# EtherCAT_Sheet.net
KiCad netlist of a schematic drawn in Altium Designer
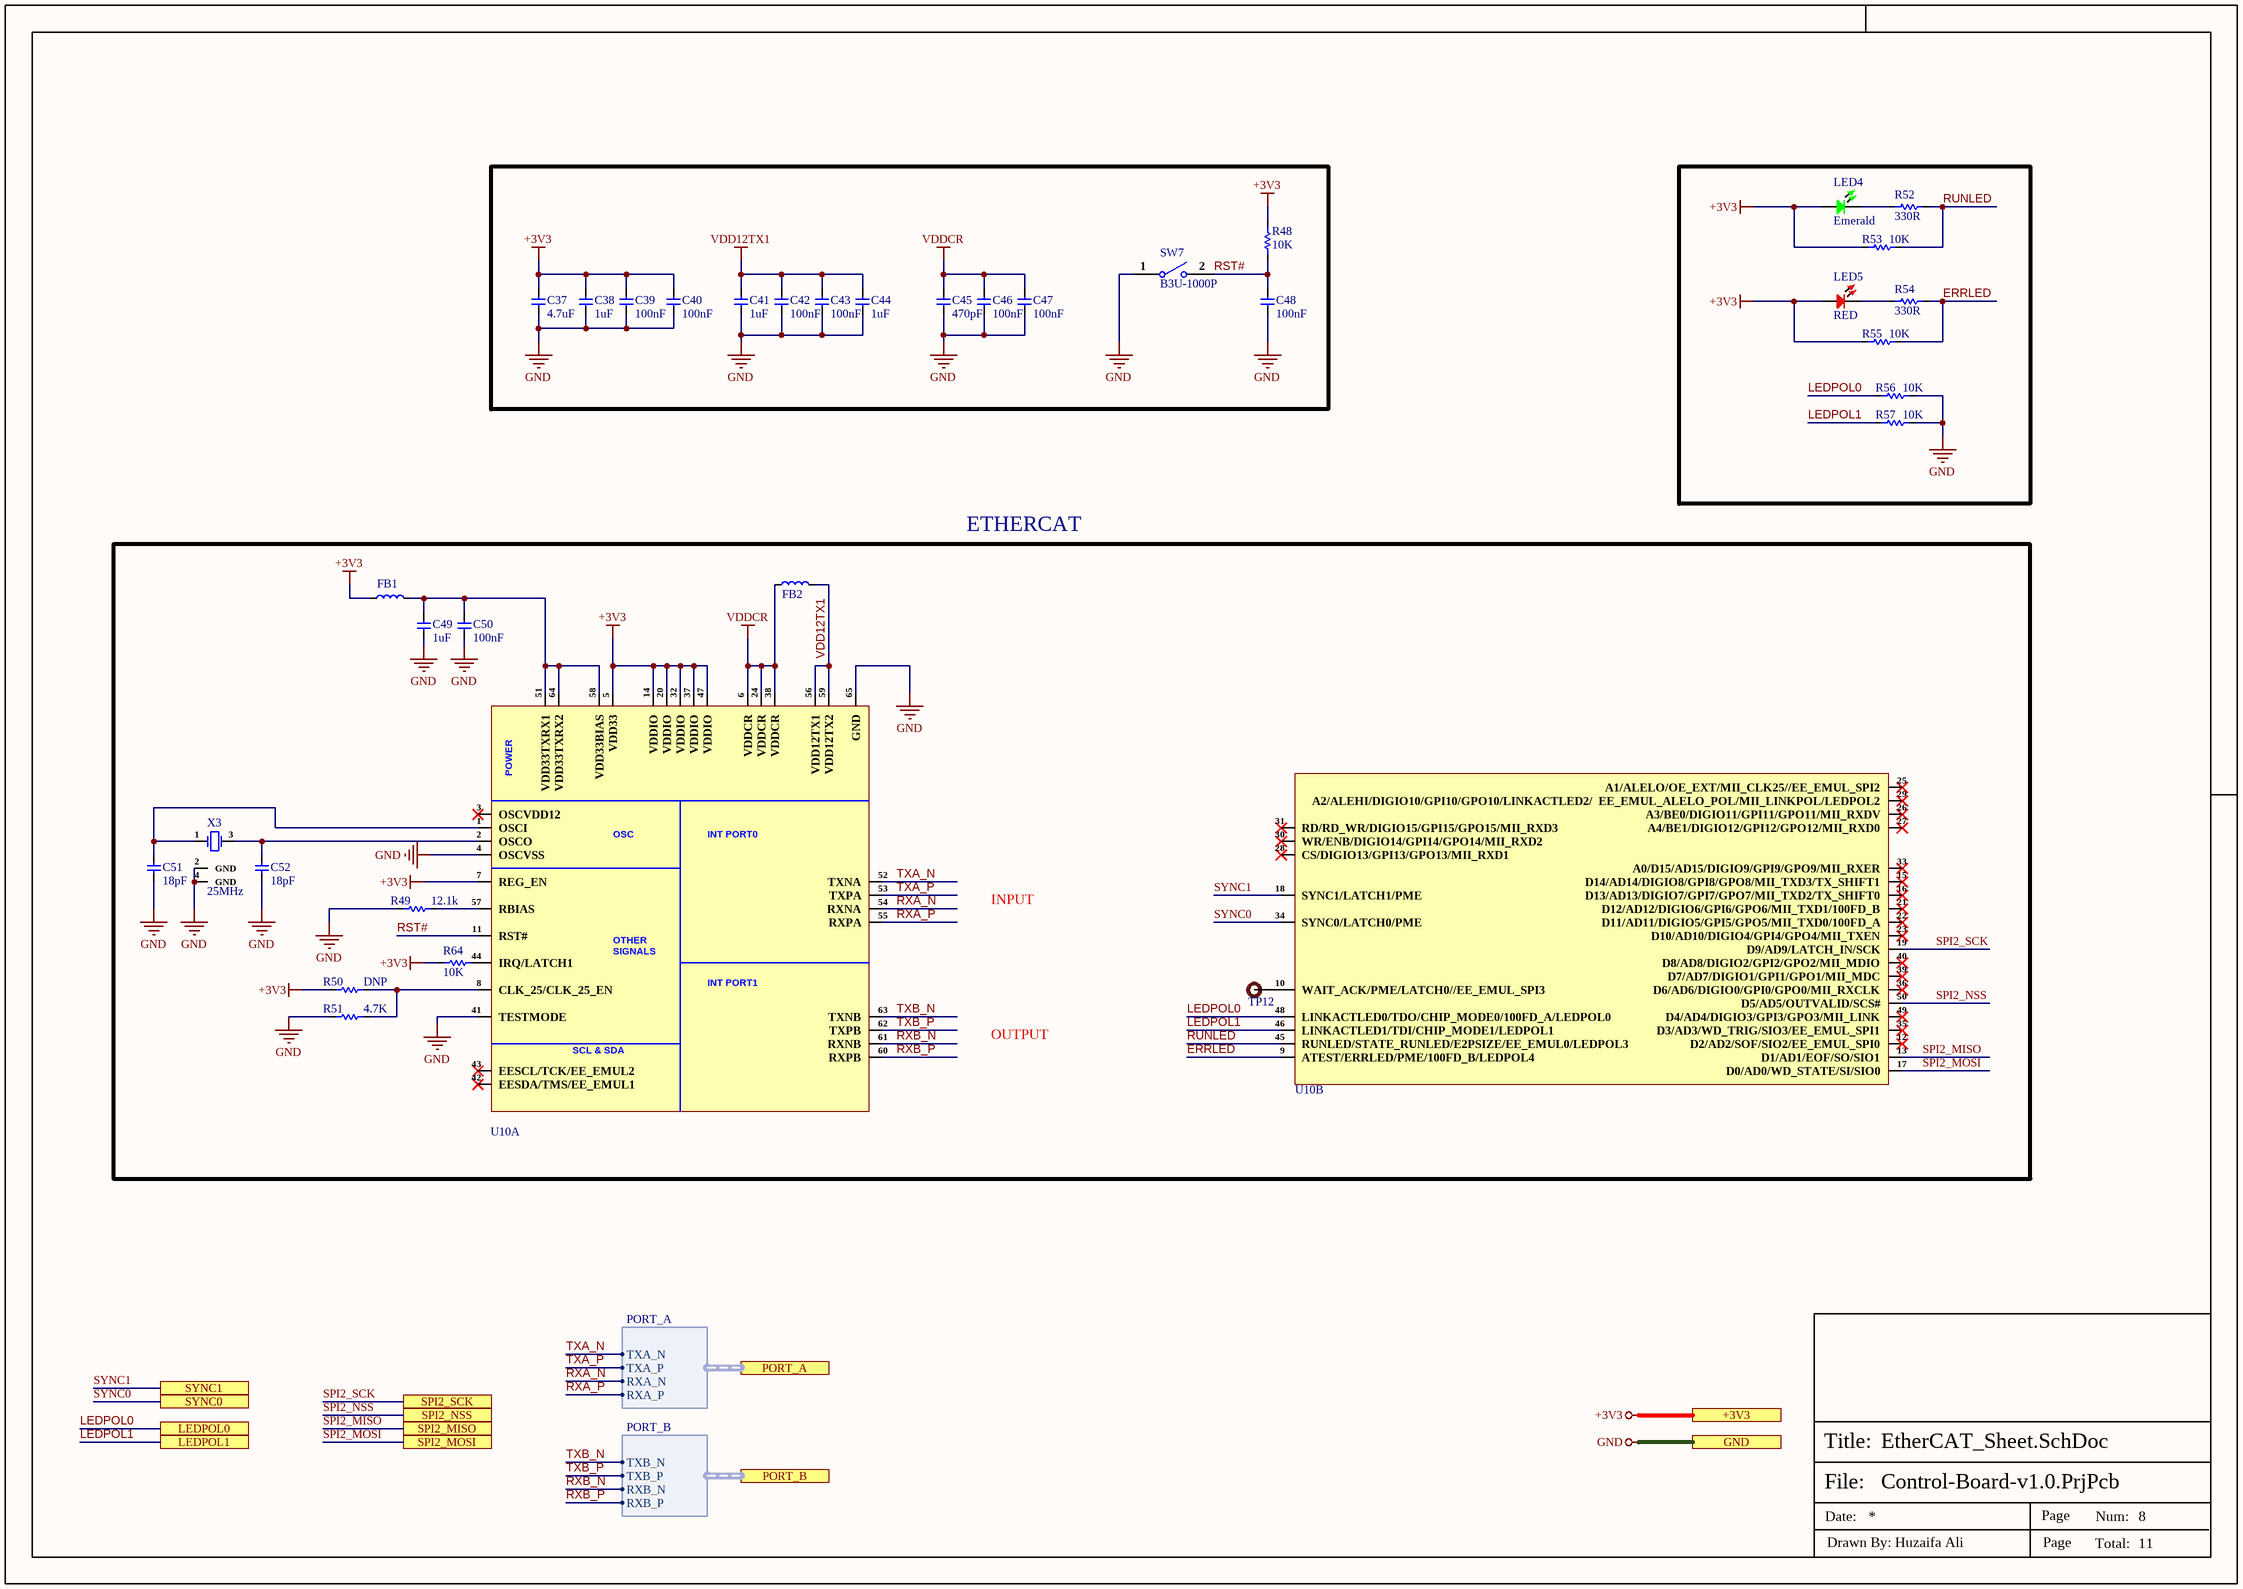
[diagram p0: EtherCAT_Sheet.SchDoc]

(export (version "E")
  (design (tool "Eeschema 10.0.6"))
  (components
    (comp (ref "C37")
      (value "4.7uF")
      (footprint "Cap-0402")
      (description "CAP CER 4.7UF 10V X5R 0402")
      (fields
        (field (name "MANUFACTURER") "Yageo")
        (field (name "MANUFACTURER PART NUMBER") "CC0402KRX5R6BB475")
      )
      (libsource (lib "eSpark Libraries") (part "CC0402KRX5R6BB475"))
    )
    (comp (ref "C38")
      (value "1uF")
      (footprint "Cap-0402")
      (description "CAP CER 1UF 10V X5R 0402")
      (fields
        (field (name "MANUFACTURER") "Yageo")
        (field (name "MANUFACTURER PART NUMBER") "CC0402KRX5R6BB105")
      )
      (libsource (lib "eSpark Libraries") (part "CC0402KRX5R6BB105"))
    )
    (comp (ref "C39")
      (value "100nF")
      (footprint "cap-0402")
      (description "CAP CER 0.1UF 50V X7R 0402")
      (fields
        (field (name "MANUFACTURER") "TDK")
        (field (name "MANUFACTURER PART NUMBER") "C1005X7R1H104KT000F")
      )
      (libsource (lib "eSpark Libraries") (part "C1005X7R1H104KT000F"))
    )
    (comp (ref "C40")
      (value "100nF")
      (footprint "cap-0402")
      (description "CAP CER 0.1UF 50V X7R 0402")
      (fields
        (field (name "MANUFACTURER") "TDK")
        (field (name "MANUFACTURER PART NUMBER") "C1005X7R1H104KT000F")
      )
      (libsource (lib "eSpark Libraries") (part "C1005X7R1H104KT000F"))
    )
    (comp (ref "C41")
      (value "1uF")
      (footprint "Cap-0402")
      (description "CAP CER 1UF 10V X5R 0402")
      (fields
        (field (name "MANUFACTURER") "Yageo")
        (field (name "MANUFACTURER PART NUMBER") "CC0402KRX5R6BB105")
      )
      (libsource (lib "eSpark Libraries") (part "CC0402KRX5R6BB105"))
    )
    (comp (ref "C42")
      (value "100nF")
      (footprint "cap-0402")
      (description "CAP CER 0.1UF 50V X7R 0402")
      (fields
        (field (name "MANUFACTURER") "TDK")
        (field (name "MANUFACTURER PART NUMBER") "C1005X7R1H104KT000F")
      )
      (libsource (lib "eSpark Libraries") (part "C1005X7R1H104KT000F"))
    )
    (comp (ref "C43")
      (value "100nF")
      (footprint "cap-0402")
      (description "CAP CER 0.1UF 50V X7R 0402")
      (fields
        (field (name "MANUFACTURER") "TDK")
        (field (name "MANUFACTURER PART NUMBER") "C1005X7R1H104KT000F")
      )
      (libsource (lib "eSpark Libraries") (part "C1005X7R1H104KT000F"))
    )
    (comp (ref "C44")
      (value "1uF")
      (footprint "Cap-0402")
      (description "CAP CER 1UF 10V X5R 0402")
      (fields
        (field (name "MANUFACTURER") "Yageo")
        (field (name "MANUFACTURER PART NUMBER") "CC0402KRX5R6BB105")
      )
      (libsource (lib "eSpark Libraries") (part "CC0402KRX5R6BB105"))
    )
    (comp (ref "C45")
      (value "470pF")
      (footprint "Cap-0603")
      (description "CAP CER 470PF 50V X7R 0603")
      (fields
        (field (name "MANUFACTURER") "Walsin Technologies")
        (field (name "MANUFACTURER PART NUMBER") "0603B471K500CT")
      )
      (libsource (lib "eSpark Libraries") (part "0603B471K500CT"))
    )
    (comp (ref "C46")
      (value "100nF")
      (footprint "cap-0402")
      (description "CAP CER 0.1UF 50V X7R 0402")
      (fields
        (field (name "MANUFACTURER") "TDK")
        (field (name "MANUFACTURER PART NUMBER") "C1005X7R1H104KT000F")
      )
      (libsource (lib "eSpark Libraries") (part "C1005X7R1H104KT000F"))
    )
    (comp (ref "C47")
      (value "100nF")
      (footprint "cap-0402")
      (description "CAP CER 0.1UF 50V X7R 0402")
      (fields
        (field (name "MANUFACTURER") "TDK")
        (field (name "MANUFACTURER PART NUMBER") "C1005X7R1H104KT000F")
      )
      (libsource (lib "eSpark Libraries") (part "C1005X7R1H104KT000F"))
    )
    (comp (ref "C48")
      (value "100nF")
      (footprint "cap-0402")
      (description "CAP CER 0.1UF 50V X7R 0402")
      (fields
        (field (name "MANUFACTURER") "TDK")
        (field (name "MANUFACTURER PART NUMBER") "C1005X7R1H104KT000F")
      )
      (libsource (lib "eSpark Libraries") (part "C1005X7R1H104KT000F"))
    )
    (comp (ref "C49")
      (value "1uF")
      (footprint "Cap-0402")
      (description "CAP CER 1UF 10V X5R 0402")
      (fields
        (field (name "MANUFACTURER") "Yageo")
        (field (name "MANUFACTURER PART NUMBER") "CC0402KRX5R6BB105")
      )
      (libsource (lib "eSpark Libraries") (part "CC0402KRX5R6BB105"))
    )
    (comp (ref "C50")
      (value "100nF")
      (footprint "cap-0402")
      (description "CAP CER 0.1UF 50V X7R 0402")
      (fields
        (field (name "MANUFACTURER") "TDK")
        (field (name "MANUFACTURER PART NUMBER") "C1005X7R1H104KT000F")
      )
      (libsource (lib "eSpark Libraries") (part "C1005X7R1H104KT000F"))
    )
    (comp (ref "C51")
      (value "18pF")
      (footprint "Cap-0402")
      (description "CAP CER 18PF 50V C0G/NP0 0402")
      (fields
        (field (name "MANUFACTURER") "Murata")
        (field (name "MANUFACTURER PART NUMBER") "GCM1555C1H180GA16D")
      )
      (libsource (lib "eSpark Libraries") (part "GCM1555C1H180GA16D"))
    )
    (comp (ref "C52")
      (value "18pF")
      (footprint "Cap-0402")
      (description "CAP CER 18PF 50V C0G/NP0 0402")
      (fields
        (field (name "MANUFACTURER") "Murata")
        (field (name "MANUFACTURER PART NUMBER") "GCM1555C1H180GA16D")
      )
      (libsource (lib "eSpark Libraries") (part "GCM1555C1H180GA16D"))
    )
    (comp (ref "FB1")
      (value "BLM15PG100SN1D")
      (footprint "IND-0402")
      (description "FERRITE BEAD 10 OHM 0402 1LN")
      (fields (field (name "MANUFACTURER") "Murata") (field (name "TOLERANCE") "25%"))
      (libsource (lib "eSpark Libraries") (part "BLM15PG100SN1D"))
    )
    (comp (ref "FB2")
      (value "BLM15PG100SN1D")
      (footprint "IND-0402")
      (description "FERRITE BEAD 10 OHM 0402 1LN")
      (fields (field (name "MANUFACTURER") "Murata") (field (name "TOLERANCE") "25%"))
      (libsource (lib "eSpark Libraries") (part "BLM15PG100SN1D"))
    )
    (comp (ref "LED4")
      (value "Emerald")
      (footprint "LED-0603")
      (description "Emerald 0603 Light Emitting Diodes (LED) ROHS")
      (fields
        (field (name "MANUFACTURER") "Foshan NationStar Optoelectronics")
        (field (name "MANUFACTURER PART NUMBER") "NCD0603G2")
      )
      (libsource (lib "eSpark Libraries") (part "NCD0603G2"))
    )
    (comp (ref "LED5")
      (value "RED")
      (footprint "LED-0603")
      (description "RED LED 0603 Light Emitting Diodes")
      (fields
        (field (name "MANUFACTURER") "Foshan NationStar Optoelectronics")
        (field (name "MANUFACTURER PART NUMBER") "NCD0603R3")
      )
      (libsource (lib "eSpark Libraries") (part "NCD0603R3"))
    )
    (comp (ref "R48")
      (value "10K")
      (footprint "Res-0402")
      (description "RES 10K OHM 1% 1/16W 0402")
      (fields
        (field (name "MANUFACTURER") "Yageo")
        (field (name "MANUFACTURER PART NUMBER") "RC0402FR-0710KL")
      )
      (libsource (lib "eSpark Libraries") (part "RC0402FR-0710KL"))
    )
    (comp (ref "R49")
      (value "12.1k")
      (footprint "Res-0402")
      (description "RES SMD 12.1KOHM 0.1% 1/16W 0402")
      (fields
        (field (name "MANUFACTURER") "Yageo")
        (field (name "MANUFACTURER PART NUMBER") "RT0402BRD0712K1L")
      )
      (libsource (lib "eSpark Libraries") (part "RT0402BRD0712K1L"))
    )
    (comp (ref "R50")
      (value "DNP")
      (footprint "Res-0402")
      (description "RES 4.7K OHM 1% 1/16W 0402")
      (fields
        (field (name "MANUFACTURER") "Yageo")
        (field (name "MANUFACTURER PART NUMBER") "RC0402FR-074K7L")
      )
      (libsource (lib "eSpark Libraries") (part "RC0402FR-074K7L"))
    )
    (comp (ref "R51")
      (value "4.7K")
      (footprint "Res-0402")
      (description "RES 4.7K OHM 1% 1/16W 0402")
      (fields
        (field (name "MANUFACTURER") "Yageo")
        (field (name "MANUFACTURER PART NUMBER") "RC0402FR-074K7L")
      )
      (libsource (lib "eSpark Libraries") (part "RC0402FR-074K7L"))
    )
    (comp (ref "R52")
      (value "330R")
      (footprint "Res-0603")
      (description "RES  SMD 330R 100 mW 0603")
      (fields
        (field (name "MANUFACTURER") "Yageo")
        (field (name "MANUFACTURER PART NUMBER") "RC0603JR-07330RL")
      )
      (libsource (lib "eSpark Libraries") (part "RC0603JR-07330RL"))
    )
    (comp (ref "R53")
      (value "10K")
      (footprint "Res-0402")
      (description "RES 10K OHM 1% 1/16W 0402")
      (fields
        (field (name "MANUFACTURER") "Yageo")
        (field (name "MANUFACTURER PART NUMBER") "RC0402FR-0710KL")
      )
      (libsource (lib "eSpark Libraries") (part "RC0402FR-0710KL"))
    )
    (comp (ref "R54")
      (value "330R")
      (footprint "Res-0603")
      (description "RES  SMD 330R 100 mW 0603")
      (fields
        (field (name "MANUFACTURER") "Yageo")
        (field (name "MANUFACTURER PART NUMBER") "RC0603JR-07330RL")
      )
      (libsource (lib "eSpark Libraries") (part "RC0603JR-07330RL"))
    )
    (comp (ref "R55")
      (value "10K")
      (footprint "Res-0402")
      (description "RES 10K OHM 1% 1/16W 0402")
      (fields
        (field (name "MANUFACTURER") "Yageo")
        (field (name "MANUFACTURER PART NUMBER") "RC0402FR-0710KL")
      )
      (libsource (lib "eSpark Libraries") (part "RC0402FR-0710KL"))
    )
    (comp (ref "R56")
      (value "10K")
      (footprint "Res-0402")
      (description "RES 10K OHM 1% 1/16W 0402")
      (fields
        (field (name "MANUFACTURER") "Yageo")
        (field (name "MANUFACTURER PART NUMBER") "RC0402FR-0710KL")
      )
      (libsource (lib "eSpark Libraries") (part "RC0402FR-0710KL"))
    )
    (comp (ref "R57")
      (value "10K")
      (footprint "Res-0402")
      (description "RES 10K OHM 1% 1/16W 0402")
      (fields
        (field (name "MANUFACTURER") "Yageo")
        (field (name "MANUFACTURER PART NUMBER") "RC0402FR-0710KL")
      )
      (libsource (lib "eSpark Libraries") (part "RC0402FR-0710KL"))
    )
    (comp (ref "R64")
      (value "10K")
      (footprint "Res-0402")
      (description "RES 10K OHM 1% 1/16W 0402")
      (fields
        (field (name "MANUFACTURER") "Yageo")
        (field (name "MANUFACTURER PART NUMBER") "RC0402FR-0710KL")
      )
      (libsource (lib "eSpark Libraries") (part "RC0402FR-0710KL"))
    )
    (comp (ref "SW7")
      (value "B3U-1000P")
      (footprint "B3U-1000P")
      (description "SWITCH TACTILE SPST-NO 0.05A 12V")
      (fields (field (name "MANUFACTURER") "Omron") (field (name "LCSC PART NUMBER") "C231329"))
      (libsource (lib "eSpark Libraries") (part "B3U-1000P"))
    )
    (comp (ref "TP12")
      (value "TEST POINT")
      (footprint "Test-point")
      (description "Test Point ON")
      (libsource (lib "eSpark Libraries") (part "TEST POINT"))
    )
    (comp (ref "U10")
      (value "LAN9253-SVB QFN64")
      (footprint "QFN-64-EP(9x9)")
      (description "2/3-PORT ETHERCAT SLAVE CTLR")
      (fields
        (field (name "MANUFACTURER") "Microchip")
        (field (name "MANUFACTURER PART NUMBER") "LAN9253-I/R4X")
      )
      (libsource (lib "eSpark Libraries") (part "LAN9253-SVB QFN64"))
    )
    (comp (ref "X3")
      (value "25MHz")
      (footprint "SMD3225-4P")
      (description "25MHz 贴片晶振 18pF ±10ppm ±20ppm SMD3225-4P Crystals ROHS")
      (fields (field (name "LCSC PART NUMBER") "C70593") (field (name "MANUFACTURER") "YXC"))
      (libsource (lib "eSpark Libraries") (part "X322525MRB4SI"))
    )
  )
  (nets
    (net (code "3") (name "+3V3") (class "Default")
      (node (ref "C37") (pin "2") (pinfunction "2_2") (pintype "passive"))
      (node (ref "C38") (pin "2") (pinfunction "2_2") (pintype "passive"))
      (node (ref "C39") (pin "2") (pinfunction "2_2") (pintype "passive"))
      (node (ref "C40") (pin "2") (pinfunction "2_2") (pintype "passive"))
      (node (ref "FB1") (pin "1") (pinfunction "1_1") (pintype "passive"))
      (node (ref "LED4") (pin "1") (pinfunction "1_1") (pintype "passive"))
      (node (ref "LED5") (pin "1") (pinfunction "1_1") (pintype "passive"))
      (node (ref "R48") (pin "1") (pinfunction "1_1") (pintype "passive"))
      (node (ref "R50") (pin "1") (pinfunction "1_1") (pintype "passive"))
      (node (ref "R53") (pin "2") (pinfunction "2_2") (pintype "passive"))
      (node (ref "R55") (pin "2") (pinfunction "2_2") (pintype "passive"))
      (node (ref "R64") (pin "1") (pinfunction "1_1") (pintype "passive"))
      (node (ref "U10") (pin "14") (pinfunction "VDDIO_14") (pintype "passive"))
      (node (ref "U10") (pin "20") (pinfunction "VDDIO_20") (pintype "passive"))
      (node (ref "U10") (pin "32") (pinfunction "VDDIO_32") (pintype "passive"))
      (node (ref "U10") (pin "37") (pinfunction "VDDIO_37") (pintype "passive"))
      (node (ref "U10") (pin "47") (pinfunction "VDDIO_47") (pintype "passive"))
      (node (ref "U10") (pin "5") (pinfunction "VDD33_5") (pintype "passive"))
      (node (ref "U10") (pin "7") (pinfunction "REG_EN_7") (pintype "passive"))
    )
    (net (code "4") (name "/ERRLED") (class "Default")
      (node (ref "R54") (pin "2") (pinfunction "2_2") (pintype "passive"))
      (node (ref "R55") (pin "1") (pinfunction "1_1") (pintype "passive"))
      (node (ref "U10") (pin "9") (pinfunction "ATEST/ERRLED/PME/100FD_B/LEDPOL4_9") (pintype "passive"))
    )
    (net (code "5") (name "/LEDPOL0") (class "Default")
      (node (ref "R56") (pin "2") (pinfunction "2_2") (pintype "passive"))
      (node (ref "U10") (pin "48") (pinfunction "LINKACTLED0/TDO/CHIP_MODE0/100FD_A/LEDPOL0_48") (pintype "passive"))
    )
    (net (code "6") (name "/LEDPOL1") (class "Default")
      (node (ref "R57") (pin "2") (pinfunction "2_2") (pintype "passive"))
      (node (ref "U10") (pin "46") (pinfunction "LINKACTLED1/TDI/CHIP_MODE1/LEDPOL1_46") (pintype "passive"))
    )
    (net (code "7") (name "/RST#") (class "Default")
      (node (ref "C48") (pin "2") (pinfunction "2_2") (pintype "passive"))
      (node (ref "R48") (pin "2") (pinfunction "2_2") (pintype "passive"))
      (node (ref "SW7") (pin "2") (pinfunction "2_2") (pintype "passive"))
      (node (ref "U10") (pin "11") (pinfunction "RST#_11") (pintype "passive"))
    )
    (net (code "8") (name "/RUNLED") (class "Default")
      (node (ref "R52") (pin "2") (pinfunction "2_2") (pintype "passive"))
      (node (ref "R53") (pin "1") (pinfunction "1_1") (pintype "passive"))
      (node (ref "U10") (pin "45") (pinfunction "RUNLED/STATE_RUNLED/E2PSIZE/EE_EMUL0/LEDPOL3_45") (pintype "passive"))
    )
    (net (code "9") (name "/RXA_N") (class "Default")
      (node (ref "U10") (pin "54") (pinfunction "RXNA_54") (pintype "passive"))
    )
    (net (code "10") (name "/RXA_P") (class "Default")
      (node (ref "U10") (pin "55") (pinfunction "RXPA_55") (pintype "passive"))
    )
    (net (code "11") (name "/RXB_N") (class "Default")
      (node (ref "U10") (pin "61") (pinfunction "RXNB_61") (pintype "passive"))
    )
    (net (code "12") (name "/RXB_P") (class "Default")
      (node (ref "U10") (pin "60") (pinfunction "RXPB_60") (pintype "passive"))
    )
    (net (code "13") (name "/SPI2_MISO") (class "Default")
      (node (ref "U10") (pin "13") (pinfunction "D1/AD1/EOF/SO/SIO1_13") (pintype "passive"))
    )
    (net (code "14") (name "/SPI2_MOSI") (class "Default")
      (node (ref "U10") (pin "17") (pinfunction "D0/AD0/WD_STATE/SI/SIO0_17") (pintype "passive"))
    )
    (net (code "15") (name "/SPI2_NSS") (class "Default")
      (node (ref "U10") (pin "50") (pinfunction "D5/AD5/OUTVALID/SCS#_50") (pintype "passive"))
    )
    (net (code "16") (name "/SPI2_SCK") (class "Default")
      (node (ref "U10") (pin "19") (pinfunction "D9/AD9/LATCH_IN/SCK_19") (pintype "passive"))
    )
    (net (code "17") (name "/SYNC0") (class "Default")
      (node (ref "U10") (pin "34") (pinfunction "SYNC0/LATCH0/PME_34") (pintype "passive"))
    )
    (net (code "18") (name "/SYNC1") (class "Default")
      (node (ref "U10") (pin "18") (pinfunction "SYNC1/LATCH1/PME_18") (pintype "passive"))
    )
    (net (code "19") (name "/TXA_N") (class "Default")
      (node (ref "U10") (pin "52") (pinfunction "TXNA_52") (pintype "passive"))
    )
    (net (code "20") (name "/TXA_P") (class "Default")
      (node (ref "U10") (pin "53") (pinfunction "TXPA_53") (pintype "passive"))
    )
    (net (code "21") (name "/TXB_N") (class "Default")
      (node (ref "U10") (pin "63") (pinfunction "TXNB_63") (pintype "passive"))
    )
    (net (code "22") (name "/TXB_P") (class "Default")
      (node (ref "U10") (pin "62") (pinfunction "TXPB_62") (pintype "passive"))
    )
    (net (code "25") (name "GND") (class "Default")
      (node (ref "C37") (pin "1") (pinfunction "1_1") (pintype "passive"))
      (node (ref "C38") (pin "1") (pinfunction "1_1") (pintype "passive"))
      (node (ref "C39") (pin "1") (pinfunction "1_1") (pintype "passive"))
      (node (ref "C40") (pin "1") (pinfunction "1_1") (pintype "passive"))
      (node (ref "C41") (pin "1") (pinfunction "1_1") (pintype "passive"))
      (node (ref "C42") (pin "1") (pinfunction "1_1") (pintype "passive"))
      (node (ref "C43") (pin "1") (pinfunction "1_1") (pintype "passive"))
      (node (ref "C44") (pin "1") (pinfunction "1_1") (pintype "passive"))
      (node (ref "C45") (pin "1") (pinfunction "1_1") (pintype "passive"))
      (node (ref "C46") (pin "1") (pinfunction "1_1") (pintype "passive"))
      (node (ref "C47") (pin "1") (pinfunction "1_1") (pintype "passive"))
      (node (ref "C48") (pin "1") (pinfunction "1_1") (pintype "passive"))
      (node (ref "C49") (pin "1") (pinfunction "1_1") (pintype "passive"))
      (node (ref "C50") (pin "1") (pinfunction "1_1") (pintype "passive"))
      (node (ref "C51") (pin "2") (pinfunction "2_2") (pintype "passive"))
      (node (ref "C52") (pin "2") (pinfunction "2_2") (pintype "passive"))
      (node (ref "R49") (pin "1") (pinfunction "1_1") (pintype "passive"))
      (node (ref "R51") (pin "1") (pinfunction "1_1") (pintype "passive"))
      (node (ref "R56") (pin "1") (pinfunction "1_1") (pintype "passive"))
      (node (ref "R57") (pin "1") (pinfunction "1_1") (pintype "passive"))
      (node (ref "SW7") (pin "1") (pinfunction "1_1") (pintype "passive"))
      (node (ref "U10") (pin "4") (pinfunction "OSCVSS_4") (pintype "passive"))
      (node (ref "U10") (pin "41") (pinfunction "TESTMODE_41") (pintype "passive"))
      (node (ref "U10") (pin "65") (pinfunction "GND_65") (pintype "passive"))
      (node (ref "X3") (pin "2") (pinfunction "GND_2") (pintype "passive"))
      (node (ref "X3") (pin "4") (pinfunction "GND_4") (pintype "passive"))
    )
    (net (code "26") (name "Net-(LED4-Pad2)") (class "Default")
      (node (ref "LED4") (pin "2") (pinfunction "2_2") (pintype "passive"))
      (node (ref "R52") (pin "1") (pinfunction "1_1") (pintype "passive"))
    )
    (net (code "27") (name "Net-(LED5-Pad2)") (class "Default")
      (node (ref "LED5") (pin "2") (pinfunction "2_2") (pintype "passive"))
      (node (ref "R54") (pin "1") (pinfunction "1_1") (pintype "passive"))
    )
    (net (code "28") (name "Net-(U10A-CLK_25{slash}CLK_25_EN)") (class "Default")
      (node (ref "R50") (pin "2") (pinfunction "2_2") (pintype "passive"))
      (node (ref "R51") (pin "2") (pinfunction "2_2") (pintype "passive"))
      (node (ref "U10") (pin "8") (pinfunction "CLK_25/CLK_25_EN_8") (pintype "passive"))
    )
    (net (code "29") (name "Net-(U10A-IRQ{slash}LATCH1)") (class "Default")
      (node (ref "R64") (pin "2") (pinfunction "2_2") (pintype "passive"))
      (node (ref "U10") (pin "44") (pinfunction "IRQ/LATCH1_44") (pintype "passive"))
    )
    (net (code "30") (name "Net-(U10A-OSCI)") (class "Default")
      (node (ref "C51") (pin "1") (pinfunction "1_1") (pintype "passive"))
      (node (ref "U10") (pin "1") (pinfunction "OSCI_1") (pintype "passive"))
      (node (ref "X3") (pin "1") (pinfunction "CRYSTAL_1") (pintype "passive"))
    )
    (net (code "31") (name "Net-(U10A-OSCO)") (class "Default")
      (node (ref "C52") (pin "1") (pinfunction "1_1") (pintype "passive"))
      (node (ref "U10") (pin "2") (pinfunction "OSCO_2") (pintype "passive"))
      (node (ref "X3") (pin "3") (pinfunction "CRYSTAL_3") (pintype "passive"))
    )
    (net (code "32") (name "Net-(U10A-RBIAS)") (class "Default")
      (node (ref "R49") (pin "2") (pinfunction "2_2") (pintype "passive"))
      (node (ref "U10") (pin "57") (pinfunction "RBIAS_57") (pintype "passive"))
    )
    (net (code "33") (name "Net-(U10A-VDD33BIAS)") (class "Default")
      (node (ref "C49") (pin "2") (pinfunction "2_2") (pintype "passive"))
      (node (ref "C50") (pin "2") (pinfunction "2_2") (pintype "passive"))
      (node (ref "FB1") (pin "2") (pinfunction "2_2") (pintype "passive"))
      (node (ref "U10") (pin "51") (pinfunction "VDD33TXRX1_51") (pintype "passive"))
      (node (ref "U10") (pin "58") (pinfunction "VDD33BIAS_58") (pintype "passive"))
      (node (ref "U10") (pin "64") (pinfunction "VDD33TXRX2_64") (pintype "passive"))
    )
    (net (code "34") (name "Net-(U10B-WAIT_ACK{slash}PME{slash}LATCH0{slash}{slash}EE_EMUL_SPI3)") (class "Default")
      (node (ref "TP12") (pin "1") (pinfunction "1_1") (pintype "passive"))
      (node (ref "U10") (pin "10") (pinfunction "WAIT_ACK/PME/LATCH0//EE_EMUL_SPI3_10") (pintype "passive"))
    )
    (net (code "35") (name "VDD12TX1") (class "Default")
      (node (ref "C41") (pin "2") (pinfunction "2_2") (pintype "passive"))
      (node (ref "C42") (pin "2") (pinfunction "2_2") (pintype "passive"))
      (node (ref "C43") (pin "2") (pinfunction "2_2") (pintype "passive"))
      (node (ref "C44") (pin "2") (pinfunction "2_2") (pintype "passive"))
      (node (ref "FB2") (pin "2") (pinfunction "2_2") (pintype "passive"))
      (node (ref "U10") (pin "56") (pinfunction "VDD12TX1_56") (pintype "passive"))
      (node (ref "U10") (pin "59") (pinfunction "VDD12TX2_59") (pintype "passive"))
    )
    (net (code "36") (name "VDDCR") (class "Default")
      (node (ref "C45") (pin "2") (pinfunction "2_2") (pintype "passive"))
      (node (ref "C46") (pin "2") (pinfunction "2_2") (pintype "passive"))
      (node (ref "C47") (pin "2") (pinfunction "2_2") (pintype "passive"))
      (node (ref "FB2") (pin "1") (pinfunction "1_1") (pintype "passive"))
      (node (ref "U10") (pin "24") (pinfunction "VDDCR_24") (pintype "passive"))
      (node (ref "U10") (pin "38") (pinfunction "VDDCR_38") (pintype "passive"))
      (node (ref "U10") (pin "6") (pinfunction "VDDCR_6") (pintype "passive"))
    )
    (net (code "37") (name "unconnected-(U10A-EESCL{slash}TCK{slash}EE_EMUL2-Pad43)") (class "Default")
      (node (ref "U10") (pin "43") (pinfunction "EESCL/TCK/EE_EMUL2_43") (pintype "passive+no_connect"))
    )
    (net (code "38") (name "unconnected-(U10A-EESDA{slash}TMS{slash}EE_EMUL1-Pad42)") (class "Default")
      (node (ref "U10") (pin "42") (pinfunction "EESDA/TMS/EE_EMUL1_42") (pintype "passive+no_connect"))
    )
    (net (code "39") (name "unconnected-(U10A-OSCVDD12-Pad3)") (class "Default")
      (node (ref "U10") (pin "3") (pinfunction "OSCVDD12_3") (pintype "passive+no_connect"))
    )
    (net (code "40") (name "unconnected-(U10B-A0{slash}D15{slash}AD15{slash}DIGIO9{slash}GPI9{slash}GPO9{slash}MII_RXER-Pad33)") (class "Default")
      (node (ref "U10") (pin "33") (pinfunction "A0/D15/AD15/DIGIO9/GPI9/GPO9/MII_RXER_33") (pintype "passive+no_connect"))
    )
    (net (code "41") (name "unconnected-(U10B-A1{slash}ALELO{slash}OE_EXT{slash}MII_CLK25{slash}{slash}EE_EMUL_SPI2-Pad25)") (class "Default")
      (node (ref "U10") (pin "25") (pinfunction "A1/ALELO/OE_EXT/MII_CLK25//EE_EMUL_SPI2_25") (pintype "passive+no_connect"))
    )
    (net (code "42") (name "unconnected-(U10B-A2{slash}ALEHI{slash}DIGIO10{slash}GPI10{slash}GPO10{slash}LINKACTLED2{slash}__EE_EMUL_ALELO_POL{slash}MII_LINKPOL{slash}LEDPOL2-Pad29)") (class "Default")
      (node (ref "U10") (pin "29") (pinfunction "A2/ALEHI/DIGIO10/GPI10/GPO10/LINKACTLED2/__EE_EMUL_ALELO_POL/MII_LINKPOL/LEDPOL2_29") (pintype "passive+no_connect"))
    )
    (net (code "43") (name "unconnected-(U10B-A3{slash}BE0{slash}DIGIO11{slash}GPI11{slash}GPO11{slash}MII_RXDV-Pad26)") (class "Default")
      (node (ref "U10") (pin "26") (pinfunction "A3/BE0/DIGIO11/GPI11/GPO11/MII_RXDV_26") (pintype "passive+no_connect"))
    )
    (net (code "44") (name "unconnected-(U10B-A4{slash}BE1{slash}DIGIO12{slash}GPI12{slash}GPO12{slash}MII_RXD0-Pad27)") (class "Default")
      (node (ref "U10") (pin "27") (pinfunction "A4/BE1/DIGIO12/GPI12/GPO12/MII_RXD0_27") (pintype "passive+no_connect"))
    )
    (net (code "45") (name "unconnected-(U10B-CS{slash}DIGIO13{slash}GPI13{slash}GPO13{slash}MII_RXD1-Pad28)") (class "Default")
      (node (ref "U10") (pin "28") (pinfunction "CS/DIGIO13/GPI13/GPO13/MII_RXD1_28") (pintype "passive+no_connect"))
    )
    (net (code "46") (name "unconnected-(U10B-D2{slash}AD2{slash}SOF{slash}SIO2{slash}EE_EMUL_SPI0-Pad12)") (class "Default")
      (node (ref "U10") (pin "12") (pinfunction "D2/AD2/SOF/SIO2/EE_EMUL_SPI0_12") (pintype "passive+no_connect"))
    )
    (net (code "47") (name "unconnected-(U10B-D3{slash}AD3{slash}WD_TRIG{slash}SIO3{slash}EE_EMUL_SPI1-Pad35)") (class "Default")
      (node (ref "U10") (pin "35") (pinfunction "D3/AD3/WD_TRIG/SIO3/EE_EMUL_SPI1_35") (pintype "passive+no_connect"))
    )
    (net (code "48") (name "unconnected-(U10B-D4{slash}AD4{slash}DIGIO3{slash}GPI3{slash}GPO3{slash}MII_LINK-Pad49)") (class "Default")
      (node (ref "U10") (pin "49") (pinfunction "D4/AD4/DIGIO3/GPI3/GPO3/MII_LINK_49") (pintype "passive+no_connect"))
    )
    (net (code "49") (name "unconnected-(U10B-D6{slash}AD6{slash}DIGIO0{slash}GPI0{slash}GPO0{slash}MII_RXCLK-Pad36)") (class "Default")
      (node (ref "U10") (pin "36") (pinfunction "D6/AD6/DIGIO0/GPI0/GPO0/MII_RXCLK_36") (pintype "passive+no_connect"))
    )
    (net (code "50") (name "unconnected-(U10B-D7{slash}AD7{slash}DIGIO1{slash}GPI1{slash}GPO1{slash}MII_MDC-Pad39)") (class "Default")
      (node (ref "U10") (pin "39") (pinfunction "D7/AD7/DIGIO1/GPI1/GPO1/MII_MDC_39") (pintype "passive+no_connect"))
    )
    (net (code "51") (name "unconnected-(U10B-D8{slash}AD8{slash}DIGIO2{slash}GPI2{slash}GPO2{slash}MII_MDIO-Pad40)") (class "Default")
      (node (ref "U10") (pin "40") (pinfunction "D8/AD8/DIGIO2/GPI2/GPO2/MII_MDIO_40") (pintype "passive+no_connect"))
    )
    (net (code "52") (name "unconnected-(U10B-D10{slash}AD10{slash}DIGIO4{slash}GPI4{slash}GPO4{slash}MII_TXEN-Pad23)") (class "Default")
      (node (ref "U10") (pin "23") (pinfunction "D10/AD10/DIGIO4/GPI4/GPO4/MII_TXEN_23") (pintype "passive+no_connect"))
    )
    (net (code "53") (name "unconnected-(U10B-D11{slash}AD11{slash}DIGIO5{slash}GPI5{slash}GPO5{slash}MII_TXD0{slash}100FD_A-Pad22)") (class "Default")
      (node (ref "U10") (pin "22") (pinfunction "D11/AD11/DIGIO5/GPI5/GPO5/MII_TXD0/100FD_A_22") (pintype "passive+no_connect"))
    )
    (net (code "54") (name "unconnected-(U10B-D12{slash}AD12{slash}DIGIO6{slash}GPI6{slash}GPO6{slash}MII_TXD1{slash}100FD_B-Pad21)") (class "Default")
      (node (ref "U10") (pin "21") (pinfunction "D12/AD12/DIGIO6/GPI6/GPO6/MII_TXD1/100FD_B_21") (pintype "passive+no_connect"))
    )
    (net (code "55") (name "unconnected-(U10B-D13{slash}AD13{slash}DIGIO7{slash}GPI7{slash}GPO7{slash}MII_TXD2{slash}TX_SHIFT0-Pad16)") (class "Default")
      (node (ref "U10") (pin "16") (pinfunction "D13/AD13/DIGIO7/GPI7/GPO7/MII_TXD2/TX_SHIFT0_16") (pintype "passive+no_connect"))
    )
    (net (code "56") (name "unconnected-(U10B-D14{slash}AD14{slash}DIGIO8{slash}GPI8{slash}GPO8{slash}MII_TXD3{slash}TX_SHIFT1-Pad15)") (class "Default")
      (node (ref "U10") (pin "15") (pinfunction "D14/AD14/DIGIO8/GPI8/GPO8/MII_TXD3/TX_SHIFT1_15") (pintype "passive+no_connect"))
    )
    (net (code "57") (name "unconnected-(U10B-RD{slash}RD_WR{slash}DIGIO15{slash}GPI15{slash}GPO15{slash}MII_RXD3-Pad31)") (class "Default")
      (node (ref "U10") (pin "31") (pinfunction "RD/RD_WR/DIGIO15/GPI15/GPO15/MII_RXD3_31") (pintype "passive+no_connect"))
    )
    (net (code "58") (name "unconnected-(U10B-WR{slash}ENB{slash}DIGIO14{slash}GPI14{slash}GPO14{slash}MII_RXD2-Pad30)") (class "Default")
      (node (ref "U10") (pin "30") (pinfunction "WR/ENB/DIGIO14/GPI14/GPO14/MII_RXD2_30") (pintype "passive+no_connect"))
    )
  )
)
